# Connectors.net
KiCad netlist of a schematic drawn in Altium Designer
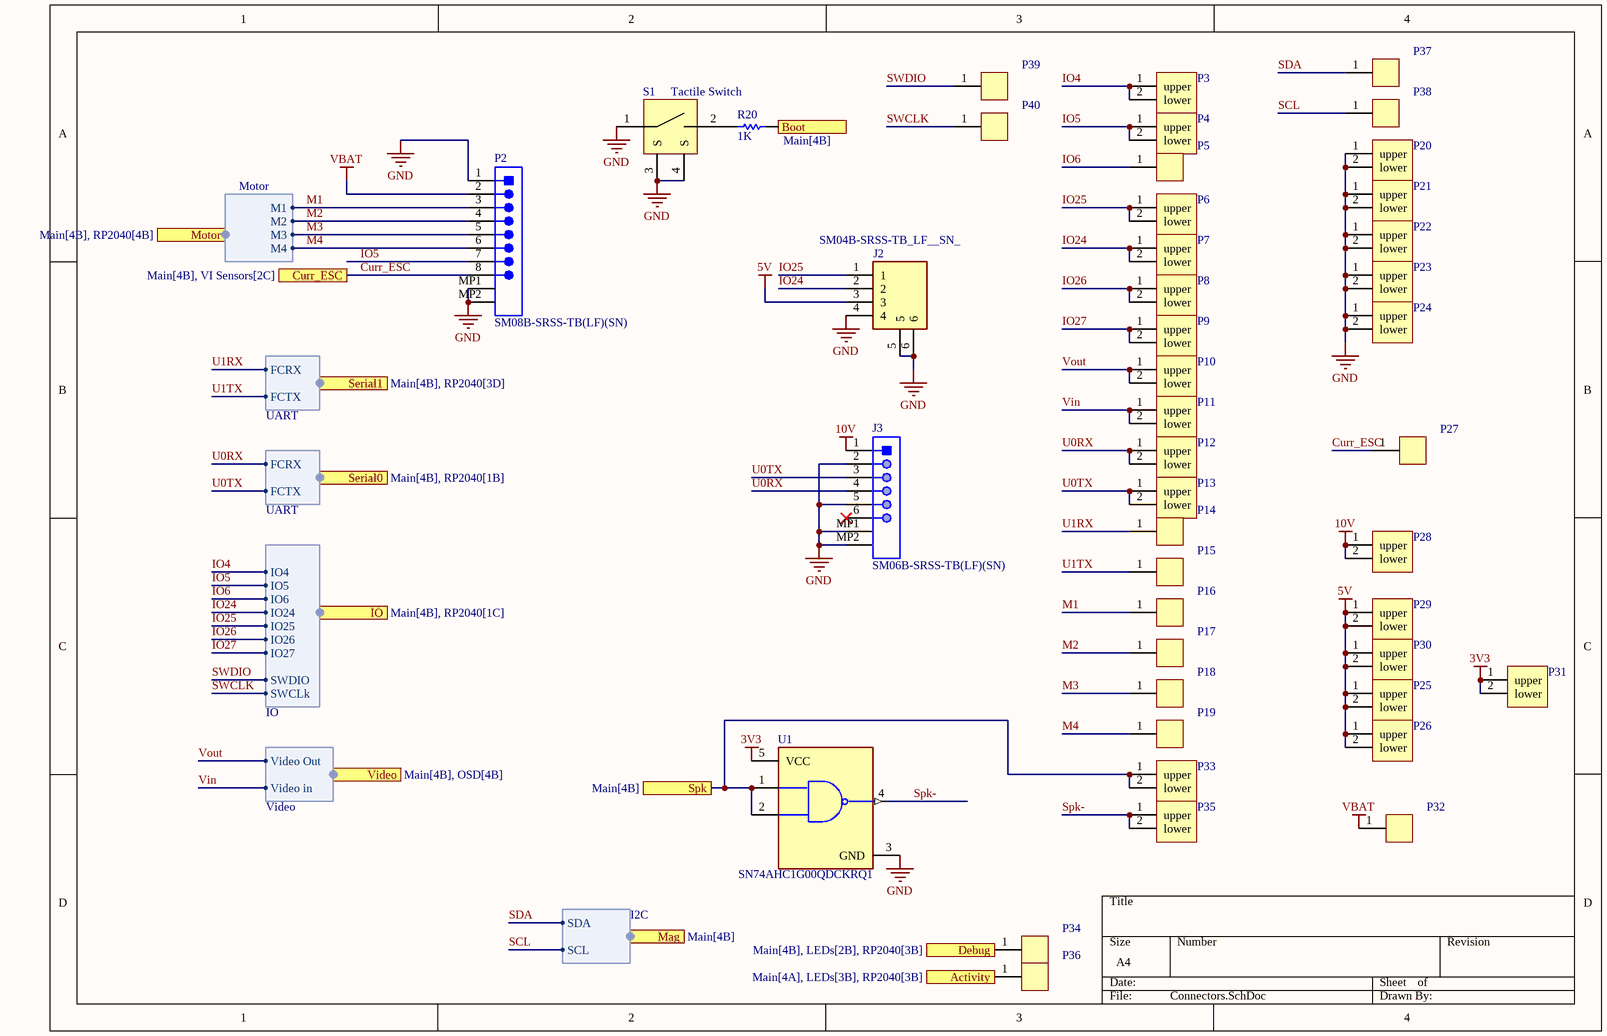
[diagram p0: Connectors.SchDoc]

(export (version "E")
  (design (tool "Eeschema 10.0.6"))
  (components
    (comp (ref "J2")
      (value "SM04B-SRSS-TB_LF__SN_")
      (footprint "SM04B-SRSS-TB(LFSN)")
      (description "Connector")
      (fields (field (name "MANUFACTURER_PART_NUMBER") "SM04B-SRSS-TB(LF)(SN)"))
      (libsource (lib "Custom Components") (part "SM04B-SRSS-TB_LF__SN_"))
    )
    (comp (ref "J3")
      (value "SM06B-SRSS-TB(LF)(SN)")
      (footprint "JST-SM06B-SRSS-TB_V")
      (description "Male Header, Pitch 1 mm, 1 x 6 Position, Height 2.95 mm, -25 to 85 degC, RoHS, Tape and Reel")
      (fields (field (name "MANUFACTURER") "JST"))
      (libsource (lib "Altium Content Vault") (part "CN-1P-2M-R6"))
    )
    (comp (ref "P2")
      (value "SM08B-SRSS-TB(LF)(SN)")
      (footprint "JST-SM08B-SRSS-TB_V")
      (description "Male Header, Pitch 1 mm, 1 x 8 Position, Height 2.95 mm, -25 to 85 degC, RoHS, Tape and Reel")
      (fields (field (name "MANUFACTURER") "JST"))
      (libsource (lib "Altium Content Vault") (part "CN-1P-2M-R8"))
    )
    (comp (ref "P3")
      (value "solder pad rounded double sided")
      (footprint "solder pad double sided rounded - duplicate")
      (libsource (lib "Custom Components") (part "solder pad rounded double sided"))
    )
    (comp (ref "P4")
      (value "solder pad rounded double sided")
      (footprint "solder pad double sided rounded - duplicate")
      (libsource (lib "Custom Components") (part "solder pad rounded double sided"))
    )
    (comp (ref "P5")
      (value "solder pad rounded single sided")
      (footprint "solder pad single sided rounded")
      (libsource (lib "Custom Components") (part "solder pad rounded single sided"))
    )
    (comp (ref "P6")
      (value "solder pad rounded double sided")
      (footprint "solder pad double sided rounded - duplicate")
      (libsource (lib "Custom Components") (part "solder pad rounded double sided"))
    )
    (comp (ref "P7")
      (value "solder pad rounded double sided")
      (footprint "solder pad double sided rounded - duplicate")
      (libsource (lib "Custom Components") (part "solder pad rounded double sided"))
    )
    (comp (ref "P8")
      (value "solder pad rounded double sided")
      (footprint "solder pad double sided rounded - duplicate")
      (libsource (lib "Custom Components") (part "solder pad rounded double sided"))
    )
    (comp (ref "P9")
      (value "solder pad rounded double sided")
      (footprint "solder pad double sided rounded - duplicate")
      (libsource (lib "Custom Components") (part "solder pad rounded double sided"))
    )
    (comp (ref "P10")
      (value "solder pad rounded double sided")
      (footprint "solder pad double sided rounded - duplicate")
      (libsource (lib "Custom Components") (part "solder pad rounded double sided"))
    )
    (comp (ref "P11")
      (value "solder pad rounded double sided")
      (footprint "solder pad double sided rounded - duplicate")
      (libsource (lib "Custom Components") (part "solder pad rounded double sided"))
    )
    (comp (ref "P12")
      (value "solder pad rounded double sided")
      (footprint "solder pad double sided rounded - duplicate")
      (libsource (lib "Custom Components") (part "solder pad rounded double sided"))
    )
    (comp (ref "P13")
      (value "solder pad rounded double sided")
      (footprint "solder pad double sided rounded - duplicate")
      (libsource (lib "Custom Components") (part "solder pad rounded double sided"))
    )
    (comp (ref "P14")
      (value "solder pad rounded single sided")
      (footprint "solder pad single sided rounded")
      (libsource (lib "Custom Components") (part "solder pad rounded single sided"))
    )
    (comp (ref "P15")
      (value "solder pad rounded single sided")
      (footprint "solder pad single sided rounded")
      (libsource (lib "Custom Components") (part "solder pad rounded single sided"))
    )
    (comp (ref "P16")
      (value "solder pad rounded single sided")
      (footprint "solder pad single sided rounded")
      (libsource (lib "Custom Components") (part "solder pad rounded single sided"))
    )
    (comp (ref "P17")
      (value "solder pad rounded single sided")
      (footprint "solder pad single sided rounded")
      (libsource (lib "Custom Components") (part "solder pad rounded single sided"))
    )
    (comp (ref "P18")
      (value "solder pad rounded single sided")
      (footprint "solder pad single sided rounded")
      (libsource (lib "Custom Components") (part "solder pad rounded single sided"))
    )
    (comp (ref "P19")
      (value "solder pad rounded single sided")
      (footprint "solder pad single sided rounded")
      (libsource (lib "Custom Components") (part "solder pad rounded single sided"))
    )
    (comp (ref "P20")
      (value "solder pad square double sided")
      (footprint "solder pad double sided square")
      (libsource (lib "Custom Components") (part "solder pad square double sided"))
    )
    (comp (ref "P21")
      (value "solder pad square double sided")
      (footprint "solder pad double sided square")
      (libsource (lib "Custom Components") (part "solder pad square double sided"))
    )
    (comp (ref "P22")
      (value "solder pad square double sided")
      (footprint "solder pad double sided square")
      (libsource (lib "Custom Components") (part "solder pad square double sided"))
    )
    (comp (ref "P23")
      (value "solder pad square double sided")
      (footprint "solder pad double sided square")
      (libsource (lib "Custom Components") (part "solder pad square double sided"))
    )
    (comp (ref "P24")
      (value "solder pad square double sided")
      (footprint "solder pad double sided square")
      (libsource (lib "Custom Components") (part "solder pad square double sided"))
    )
    (comp (ref "P25")
      (value "solder pad chamfered double sided")
      (footprint "solder pad double sided chamfered")
      (libsource (lib "Custom Components") (part "solder pad chamfered double sided"))
    )
    (comp (ref "P26")
      (value "solder pad chamfered double sided")
      (footprint "solder pad double sided chamfered")
      (libsource (lib "Custom Components") (part "solder pad chamfered double sided"))
    )
    (comp (ref "P27")
      (value "solder pad rounded single sided")
      (footprint "solder pad single sided rounded")
      (libsource (lib "Custom Components") (part "solder pad rounded single sided"))
    )
    (comp (ref "P28")
      (value "solder pad chamfered double sided")
      (footprint "solder pad double sided chamfered")
      (libsource (lib "Custom Components") (part "solder pad chamfered double sided"))
    )
    (comp (ref "P29")
      (value "solder pad chamfered double sided")
      (footprint "solder pad double sided chamfered")
      (libsource (lib "Custom Components") (part "solder pad chamfered double sided"))
    )
    (comp (ref "P30")
      (value "solder pad chamfered double sided")
      (footprint "solder pad double sided chamfered")
      (libsource (lib "Custom Components") (part "solder pad chamfered double sided"))
    )
    (comp (ref "P31")
      (value "solder pad chamfered double sided")
      (footprint "solder pad double sided chamfered")
      (libsource (lib "Custom Components") (part "solder pad chamfered double sided"))
    )
    (comp (ref "P32")
      (value "solder pad chamfered single sided")
      (footprint "solder pad single sided chamfered")
      (libsource (lib "Custom Components") (part "solder pad chamfered single sided"))
    )
    (comp (ref "P33")
      (value "solder pad rounded double sided")
      (footprint "solder pad double sided rounded - duplicate")
      (libsource (lib "Custom Components") (part "solder pad rounded double sided"))
    )
    (comp (ref "P34")
      (value "solder pad rounded single sided")
      (footprint "solder pad single sided rounded")
      (libsource (lib "Custom Components") (part "solder pad rounded single sided"))
    )
    (comp (ref "P35")
      (value "solder pad rounded double sided")
      (footprint "solder pad double sided rounded - duplicate")
      (libsource (lib "Custom Components") (part "solder pad rounded double sided"))
    )
    (comp (ref "P36")
      (value "solder pad rounded single sided")
      (footprint "solder pad single sided rounded")
      (libsource (lib "Custom Components") (part "solder pad rounded single sided"))
    )
    (comp (ref "P37")
      (value "solder pad rounded single sided")
      (footprint "solder pad single sided rounded")
      (libsource (lib "Custom Components") (part "solder pad rounded single sided"))
    )
    (comp (ref "P38")
      (value "solder pad rounded single sided")
      (footprint "solder pad single sided rounded")
      (libsource (lib "Custom Components") (part "solder pad rounded single sided"))
    )
    (comp (ref "P39")
      (value "solder pad rounded single sided")
      (footprint "solder pad single sided rounded")
      (libsource (lib "Custom Components") (part "solder pad rounded single sided"))
    )
    (comp (ref "P40")
      (value "solder pad rounded single sided")
      (footprint "solder pad single sided rounded")
      (libsource (lib "Custom Components") (part "solder pad rounded single sided"))
    )
    (comp (ref "R20")
      (value "1K")
      (footprint "Custom Components:0402 resistor")
      (libsource (lib "Custom Components") (part "Resistor 0402 1K"))
    )
    (comp (ref "S1")
      (value "Tactile Switch")
      (footprint "Tactile Switch")
      (libsource (lib "Custom Components") (part "Tactile Switch"))
    )
    (comp (ref "U1")
      (value "SN74AHC1G00QDCKRQ1")
      (footprint "FP-DCK0005A-IPC_A")
      (description "IC GATE NAND 1CH 2-INP SC70-5")
      (libsource (lib "Altium Content Vault") (part "4a1d673274a90161e31fa41c5f74738"))
    )
  )
  (nets
    (net (code "6") (name "/Activity") (class "Default")
      (node (ref "P36") (pin "1") (pinfunction "upper_1") (pintype "passive"))
    )
    (net (code "7") (name "/Boot") (class "Default")
      (node (ref "R20") (pin "2") (pinfunction "2_2") (pintype "passive"))
    )
    (net (code "8") (name "/Curr_ESC") (class "Default")
      (node (ref "P2") (pin "8") (pinfunction "8_8") (pintype "passive"))
      (node (ref "P27") (pin "1") (pinfunction "upper_1") (pintype "passive"))
    )
    (net (code "9") (name "/Debug") (class "Default")
      (node (ref "P34") (pin "1") (pinfunction "upper_1") (pintype "passive"))
    )
    (net (code "10") (name "/IO4") (class "Default")
      (node (ref "P3") (pin "1") (pinfunction "upper_1") (pintype "passive"))
      (node (ref "P3") (pin "2") (pinfunction "lower_2") (pintype "passive"))
    )
    (net (code "11") (name "/IO5") (class "Default")
      (node (ref "P2") (pin "7") (pinfunction "7_7") (pintype "passive"))
      (node (ref "P4") (pin "1") (pinfunction "upper_1") (pintype "passive"))
      (node (ref "P4") (pin "2") (pinfunction "lower_2") (pintype "passive"))
    )
    (net (code "12") (name "/IO6") (class "Default")
      (node (ref "P5") (pin "1") (pinfunction "upper_1") (pintype "passive"))
    )
    (net (code "13") (name "/IO24") (class "Default")
      (node (ref "J2") (pin "2") (pinfunction "2_2") (pintype "passive"))
      (node (ref "P7") (pin "1") (pinfunction "upper_1") (pintype "passive"))
      (node (ref "P7") (pin "2") (pinfunction "lower_2") (pintype "passive"))
    )
    (net (code "14") (name "/IO25") (class "Default")
      (node (ref "J2") (pin "1") (pinfunction "1_1") (pintype "passive"))
      (node (ref "P6") (pin "1") (pinfunction "upper_1") (pintype "passive"))
      (node (ref "P6") (pin "2") (pinfunction "lower_2") (pintype "passive"))
    )
    (net (code "15") (name "/IO26") (class "Default")
      (node (ref "P8") (pin "1") (pinfunction "upper_1") (pintype "passive"))
      (node (ref "P8") (pin "2") (pinfunction "lower_2") (pintype "passive"))
    )
    (net (code "16") (name "/IO27") (class "Default")
      (node (ref "P9") (pin "1") (pinfunction "upper_1") (pintype "passive"))
      (node (ref "P9") (pin "2") (pinfunction "lower_2") (pintype "passive"))
    )
    (net (code "17") (name "/M1") (class "Default")
      (node (ref "P16") (pin "1") (pinfunction "upper_1") (pintype "passive"))
      (node (ref "P2") (pin "3") (pinfunction "3_3") (pintype "passive"))
    )
    (net (code "18") (name "/M2") (class "Default")
      (node (ref "P17") (pin "1") (pinfunction "upper_1") (pintype "passive"))
      (node (ref "P2") (pin "4") (pinfunction "4_4") (pintype "passive"))
    )
    (net (code "19") (name "/M3") (class "Default")
      (node (ref "P18") (pin "1") (pinfunction "upper_1") (pintype "passive"))
      (node (ref "P2") (pin "5") (pinfunction "5_5") (pintype "passive"))
    )
    (net (code "20") (name "/M4") (class "Default")
      (node (ref "P19") (pin "1") (pinfunction "upper_1") (pintype "passive"))
      (node (ref "P2") (pin "6") (pinfunction "6_6") (pintype "passive"))
    )
    (net (code "21") (name "/SCL") (class "Default")
      (node (ref "P38") (pin "1") (pinfunction "upper_1") (pintype "passive"))
    )
    (net (code "22") (name "/SDA") (class "Default")
      (node (ref "P37") (pin "1") (pinfunction "upper_1") (pintype "passive"))
    )
    (net (code "23") (name "/SWCLK") (class "Default")
      (node (ref "P40") (pin "1") (pinfunction "upper_1") (pintype "passive"))
    )
    (net (code "24") (name "/SWDIO") (class "Default")
      (node (ref "P39") (pin "1") (pinfunction "upper_1") (pintype "passive"))
    )
    (net (code "25") (name "/Spk") (class "Default")
      (node (ref "P33") (pin "1") (pinfunction "upper_1") (pintype "passive"))
      (node (ref "P33") (pin "2") (pinfunction "lower_2") (pintype "passive"))
      (node (ref "U1") (pin "1") (pinfunction "A_1") (pintype "passive"))
      (node (ref "U1") (pin "2") (pinfunction "B_2") (pintype "passive"))
    )
    (net (code "26") (name "/Spk-") (class "Default")
      (node (ref "P35") (pin "1") (pinfunction "upper_1") (pintype "passive"))
      (node (ref "P35") (pin "2") (pinfunction "lower_2") (pintype "passive"))
      (node (ref "U1") (pin "4") (pinfunction "Y_4") (pintype "output"))
    )
    (net (code "27") (name "/U0RX") (class "Default")
      (node (ref "J3") (pin "4") (pinfunction "4_4") (pintype "passive"))
      (node (ref "P12") (pin "1") (pinfunction "upper_1") (pintype "passive"))
      (node (ref "P12") (pin "2") (pinfunction "lower_2") (pintype "passive"))
    )
    (net (code "28") (name "/U0TX") (class "Default")
      (node (ref "J3") (pin "3") (pinfunction "3_3") (pintype "passive"))
      (node (ref "P13") (pin "1") (pinfunction "upper_1") (pintype "passive"))
      (node (ref "P13") (pin "2") (pinfunction "lower_2") (pintype "passive"))
    )
    (net (code "29") (name "/U1RX") (class "Default")
      (node (ref "P14") (pin "1") (pinfunction "upper_1") (pintype "passive"))
    )
    (net (code "30") (name "/U1TX") (class "Default")
      (node (ref "P15") (pin "1") (pinfunction "upper_1") (pintype "passive"))
    )
    (net (code "31") (name "/Vin") (class "Default")
      (node (ref "P11") (pin "1") (pinfunction "upper_1") (pintype "passive"))
      (node (ref "P11") (pin "2") (pinfunction "lower_2") (pintype "passive"))
    )
    (net (code "32") (name "/Vout") (class "Default")
      (node (ref "P10") (pin "1") (pinfunction "upper_1") (pintype "passive"))
      (node (ref "P10") (pin "2") (pinfunction "lower_2") (pintype "passive"))
    )
    (net (code "38") (name "3V3") (class "Default")
      (node (ref "P31") (pin "1") (pinfunction "upper_1") (pintype "passive"))
      (node (ref "P31") (pin "2") (pinfunction "lower_2") (pintype "passive"))
      (node (ref "U1") (pin "5") (pinfunction "VCC_5") (pintype "power_in"))
    )
    (net (code "39") (name "5V") (class "Default")
      (node (ref "J2") (pin "3") (pinfunction "3_3") (pintype "passive"))
      (node (ref "P25") (pin "1") (pinfunction "upper_1") (pintype "passive"))
      (node (ref "P25") (pin "2") (pinfunction "lower_2") (pintype "passive"))
      (node (ref "P26") (pin "1") (pinfunction "upper_1") (pintype "passive"))
      (node (ref "P26") (pin "2") (pinfunction "lower_2") (pintype "passive"))
      (node (ref "P29") (pin "1") (pinfunction "upper_1") (pintype "passive"))
      (node (ref "P29") (pin "2") (pinfunction "lower_2") (pintype "passive"))
      (node (ref "P30") (pin "1") (pinfunction "upper_1") (pintype "passive"))
      (node (ref "P30") (pin "2") (pinfunction "lower_2") (pintype "passive"))
    )
    (net (code "40") (name "10V") (class "Default")
      (node (ref "J3") (pin "1") (pinfunction "1_1") (pintype "passive"))
      (node (ref "P28") (pin "1") (pinfunction "upper_1") (pintype "passive"))
      (node (ref "P28") (pin "2") (pinfunction "lower_2") (pintype "passive"))
    )
    (net (code "41") (name "GND") (class "Default")
      (node (ref "J2") (pin "4") (pinfunction "4_4") (pintype "passive"))
      (node (ref "J2") (pin "5") (pinfunction "5_5") (pintype "passive"))
      (node (ref "J2") (pin "6") (pinfunction "6_6") (pintype "passive"))
      (node (ref "J3") (pin "2") (pinfunction "2_2") (pintype "passive"))
      (node (ref "J3") (pin "5") (pinfunction "5_5") (pintype "passive"))
      (node (ref "J3") (pin "MP1") (pinfunction "MP1_MP1") (pintype "passive"))
      (node (ref "J3") (pin "MP2") (pinfunction "MP2_MP2") (pintype "passive"))
      (node (ref "P2") (pin "1") (pinfunction "1_1") (pintype "passive"))
      (node (ref "P2") (pin "MP1") (pinfunction "MP1_MP1") (pintype "passive"))
      (node (ref "P2") (pin "MP2") (pinfunction "MP2_MP2") (pintype "passive"))
      (node (ref "P20") (pin "1") (pinfunction "upper_1") (pintype "passive"))
      (node (ref "P20") (pin "2") (pinfunction "lower_2") (pintype "passive"))
      (node (ref "P21") (pin "1") (pinfunction "upper_1") (pintype "passive"))
      (node (ref "P21") (pin "2") (pinfunction "lower_2") (pintype "passive"))
      (node (ref "P22") (pin "1") (pinfunction "upper_1") (pintype "passive"))
      (node (ref "P22") (pin "2") (pinfunction "lower_2") (pintype "passive"))
      (node (ref "P23") (pin "1") (pinfunction "upper_1") (pintype "passive"))
      (node (ref "P23") (pin "2") (pinfunction "lower_2") (pintype "passive"))
      (node (ref "P24") (pin "1") (pinfunction "upper_1") (pintype "passive"))
      (node (ref "P24") (pin "2") (pinfunction "lower_2") (pintype "passive"))
      (node (ref "S1") (pin "1") (pintype "passive"))
      (node (ref "S1") (pin "3") (pinfunction "S_3") (pintype "passive"))
      (node (ref "S1") (pin "4") (pinfunction "S_4") (pintype "passive"))
      (node (ref "U1") (pin "3") (pinfunction "GND_3") (pintype "power_in"))
    )
    (net (code "42") (name "Net-(R20-Pad1)") (class "Default")
      (node (ref "R20") (pin "1") (pinfunction "1_1") (pintype "passive"))
      (node (ref "S1") (pin "2") (pintype "passive"))
    )
    (net (code "43") (name "VBAT") (class "Default")
      (node (ref "P2") (pin "2") (pinfunction "2_2") (pintype "passive"))
      (node (ref "P32") (pin "1") (pinfunction "upper_1") (pintype "passive"))
    )
    (net (code "44") (name "unconnected-(J3-Pad6)") (class "Default")
      (node (ref "J3") (pin "6") (pinfunction "6_6") (pintype "passive+no_connect"))
    )
  )
)
